# motoko_ice_dragon_x_bldc.net
KiCad netlist of a schematic drawn in EAGLE
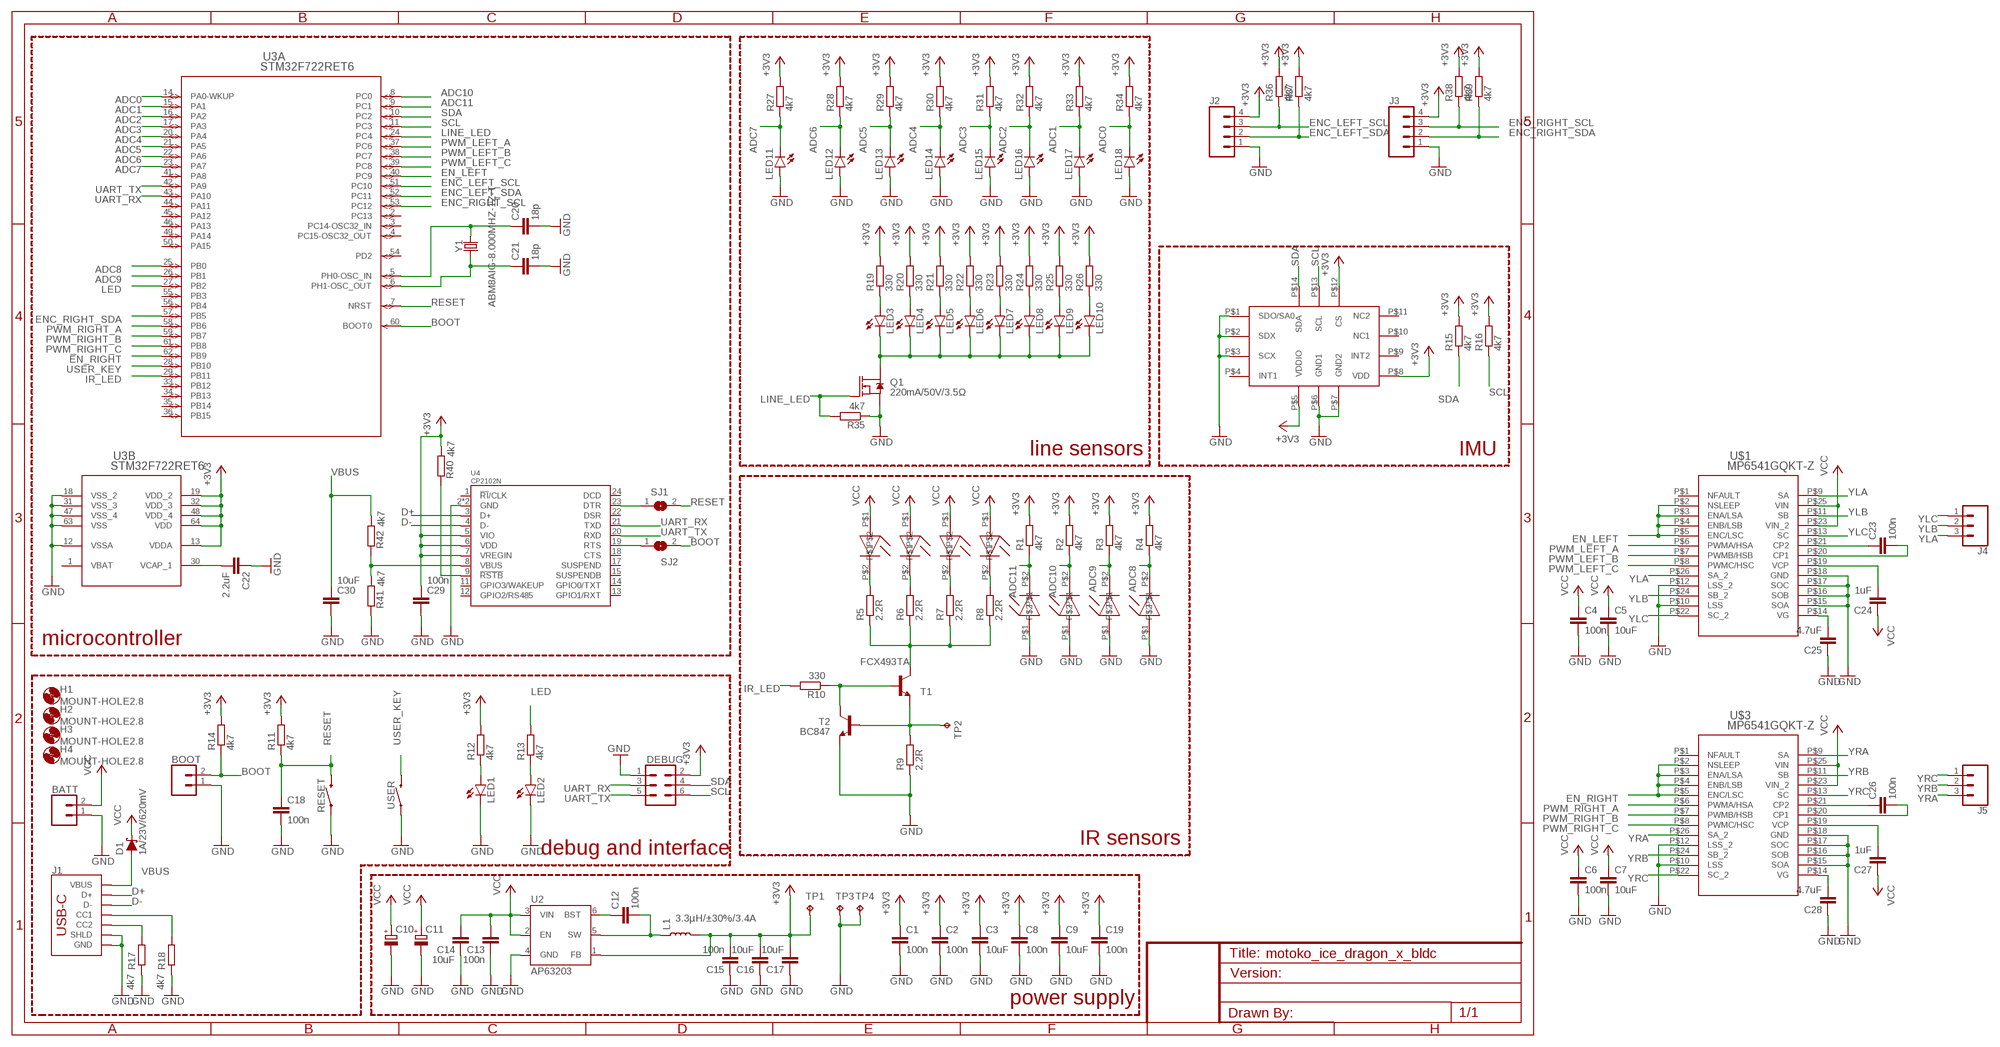
[diagram p0: schematic, sheet 1]

(export (version "E")
  (design (tool "Eeschema 10.0.6"))
  (components
    (comp (ref "BATT")
      (value "CONN_02LOCK_LONGPADS")
      (footprint "eagle-import:1X02_LOCK_LONGPADS")
      (libsource (lib "eagle-import") (part "CONN_02LOCK_LONGPADS"))
    )
    (comp (ref "BOOT")
      (value "CONN_02LOCK_LONGPADS")
      (footprint "eagle-import:1X02_LOCK_LONGPADS")
      (libsource (lib "eagle-import") (part "CONN_02LOCK_LONGPADS"))
    )
    (comp (ref "C1")
      (value "100n")
      (footprint "eagle-import:C0805")
      (libsource (lib "eagle-import") (part "C-EUC0805"))
    )
    (comp (ref "C2")
      (value "100n")
      (footprint "eagle-import:C0805")
      (libsource (lib "eagle-import") (part "C-EUC0805"))
    )
    (comp (ref "C3")
      (value "10uF")
      (footprint "eagle-import:C0805")
      (libsource (lib "eagle-import") (part "C-EUC0805"))
    )
    (comp (ref "C4")
      (value "100n")
      (footprint "eagle-import:C0805")
      (libsource (lib "eagle-import") (part "C-EUC0805"))
    )
    (comp (ref "C5")
      (value "10uF")
      (footprint "eagle-import:C0805")
      (libsource (lib "eagle-import") (part "C-EUC0805"))
    )
    (comp (ref "C6")
      (value "100n")
      (footprint "eagle-import:C0805")
      (libsource (lib "eagle-import") (part "C-EUC0805"))
    )
    (comp (ref "C7")
      (value "10uF")
      (footprint "eagle-import:C0805")
      (libsource (lib "eagle-import") (part "C-EUC0805"))
    )
    (comp (ref "C8")
      (value "100n")
      (footprint "eagle-import:C0805")
      (libsource (lib "eagle-import") (part "C-EUC0805"))
    )
    (comp (ref "C9")
      (value "10uF")
      (footprint "eagle-import:C0805")
      (libsource (lib "eagle-import") (part "C-EUC0805"))
    )
    (comp (ref "C10")
      (value "CPOL-EU140CLH-0810")
      (footprint "eagle-import:140CLH-0810")
      (libsource (lib "eagle-import") (part "CPOL-EU140CLH-0810"))
    )
    (comp (ref "C11")
      (value "CPOL-EU140CLH-0810")
      (footprint "eagle-import:140CLH-0810")
      (libsource (lib "eagle-import") (part "CPOL-EU140CLH-0810"))
    )
    (comp (ref "C12")
      (value "100n")
      (footprint "eagle-import:C0805")
      (libsource (lib "eagle-import") (part "C-EUC0805"))
    )
    (comp (ref "C13")
      (value "100n")
      (footprint "eagle-import:C0805")
      (libsource (lib "eagle-import") (part "C-EUC0805"))
    )
    (comp (ref "C14")
      (value "10uF")
      (footprint "eagle-import:C0805")
      (libsource (lib "eagle-import") (part "C-EUC0805"))
    )
    (comp (ref "C15")
      (value "100n")
      (footprint "eagle-import:C0805")
      (libsource (lib "eagle-import") (part "C-EUC0805"))
    )
    (comp (ref "C16")
      (value "10uF")
      (footprint "eagle-import:C0805")
      (libsource (lib "eagle-import") (part "C-EUC0805"))
    )
    (comp (ref "C17")
      (value "10uF")
      (footprint "eagle-import:C0805")
      (libsource (lib "eagle-import") (part "C-EUC0805"))
    )
    (comp (ref "C18")
      (value "100n")
      (footprint "eagle-import:C0805")
      (libsource (lib "eagle-import") (part "C-EUC0805"))
    )
    (comp (ref "C19")
      (value "100n")
      (footprint "eagle-import:C0805")
      (libsource (lib "eagle-import") (part "C-EUC0805"))
    )
    (comp (ref "C20")
      (value "18p")
      (footprint "eagle-import:C0805")
      (libsource (lib "eagle-import") (part "C-EUC0805"))
    )
    (comp (ref "C21")
      (value "18p")
      (footprint "eagle-import:C0805")
      (libsource (lib "eagle-import") (part "C-EUC0805"))
    )
    (comp (ref "C22")
      (value "2.2uF")
      (footprint "eagle-import:C0805")
      (libsource (lib "eagle-import") (part "C-EUC0805"))
    )
    (comp (ref "C23")
      (value "100n")
      (footprint "eagle-import:C0805")
      (libsource (lib "eagle-import") (part "C-EUC0805"))
    )
    (comp (ref "C24")
      (value "1uF")
      (footprint "eagle-import:C0805")
      (libsource (lib "eagle-import") (part "C-EUC0805"))
    )
    (comp (ref "C25")
      (value "4.7uF")
      (footprint "eagle-import:C0805")
      (libsource (lib "eagle-import") (part "C-EUC0805"))
    )
    (comp (ref "C26")
      (value "100n")
      (footprint "eagle-import:C0805")
      (libsource (lib "eagle-import") (part "C-EUC0805"))
    )
    (comp (ref "C27")
      (value "1uF")
      (footprint "eagle-import:C0805")
      (libsource (lib "eagle-import") (part "C-EUC0805"))
    )
    (comp (ref "C28")
      (value "4.7uF")
      (footprint "eagle-import:C0805")
      (libsource (lib "eagle-import") (part "C-EUC0805"))
    )
    (comp (ref "C29")
      (value "100n")
      (footprint "eagle-import:C0805")
      (libsource (lib "eagle-import") (part "C-EUC0805"))
    )
    (comp (ref "C30")
      (value "10uF")
      (footprint "eagle-import:C0805")
      (libsource (lib "eagle-import") (part "C-EUC0805"))
    )
    (comp (ref "D1")
      (value "1A/23V/620mV")
      (footprint "eagle-import:SOD-323")
      (libsource (lib "eagle-import") (part "DIODE-SCHOTTKY-BAT20J"))
    )
    (comp (ref "DEBUG")
      (value "FEMALE 2x3")
      (footprint "eagle-import:2X3")
      (libsource (lib "eagle-import") (part "CONN_03X2FEMALE"))
    )
    (comp (ref "H1")
      (value "MOUNT-HOLE2.8")
      (footprint "eagle-import:2,8")
      (libsource (lib "eagle-import") (part "MOUNT-HOLE2.8"))
    )
    (comp (ref "H2")
      (value "MOUNT-HOLE2.8")
      (footprint "eagle-import:2,8")
      (libsource (lib "eagle-import") (part "MOUNT-HOLE2.8"))
    )
    (comp (ref "H3")
      (value "MOUNT-HOLE2.8")
      (footprint "eagle-import:2,8")
      (libsource (lib "eagle-import") (part "MOUNT-HOLE2.8"))
    )
    (comp (ref "H4")
      (value "MOUNT-HOLE2.8")
      (footprint "eagle-import:2,8")
      (libsource (lib "eagle-import") (part "MOUNT-HOLE2.8"))
    )
    (comp (ref "J1")
      (value "640-USB4105-GF-A-120, man. GCT")
      (footprint "eagle-import:USB-C-16P-2LAYER-PADS")
      (libsource (lib "eagle-import") (part "USB_C_2-LAYER_PADS"))
    )
    (comp (ref "J2")
      (value "CONN_04LONGPADS")
      (footprint "eagle-import:1X04_LONGPADS")
      (libsource (lib "eagle-import") (part "CONN_04LONGPADS"))
    )
    (comp (ref "J3")
      (value "CONN_04LONGPADS")
      (footprint "eagle-import:1X04_LONGPADS")
      (libsource (lib "eagle-import") (part "CONN_04LONGPADS"))
    )
    (comp (ref "J4")
      (value "CONN_03LONGPADS")
      (footprint "eagle-import:1X03_LONGPADS")
      (libsource (lib "eagle-import") (part "CONN_03LONGPADS"))
    )
    (comp (ref "J5")
      (value "CONN_03LONGPADS")
      (footprint "eagle-import:1X03_LONGPADS")
      (libsource (lib "eagle-import") (part "CONN_03LONGPADS"))
    )
    (comp (ref "L1")
      (value "3.3µH/±30%/3.4A")
      (footprint "eagle-import:CR54")
      (libsource (lib "eagle-import") (part "INDUCTOR-CR54-3.3UH"))
    )
    (comp (ref "LED1")
      (value "LEDCHIPLED_1206")
      (footprint "eagle-import:CHIPLED_1206")
      (libsource (lib "eagle-import") (part "LEDCHIPLED_1206"))
    )
    (comp (ref "LED2")
      (value "LEDCHIPLED_1206")
      (footprint "eagle-import:CHIPLED_1206")
      (libsource (lib "eagle-import") (part "LEDCHIPLED_1206"))
    )
    (comp (ref "LED3")
      (value "LEDCHIPLED_1206")
      (footprint "eagle-import:CHIPLED_1206")
      (libsource (lib "eagle-import") (part "LEDCHIPLED_1206"))
    )
    (comp (ref "LED4")
      (value "LEDCHIPLED_1206")
      (footprint "eagle-import:CHIPLED_1206")
      (libsource (lib "eagle-import") (part "LEDCHIPLED_1206"))
    )
    (comp (ref "LED5")
      (value "LEDCHIPLED_1206")
      (footprint "eagle-import:CHIPLED_1206")
      (libsource (lib "eagle-import") (part "LEDCHIPLED_1206"))
    )
    (comp (ref "LED6")
      (value "LEDCHIPLED_1206")
      (footprint "eagle-import:CHIPLED_1206")
      (libsource (lib "eagle-import") (part "LEDCHIPLED_1206"))
    )
    (comp (ref "LED7")
      (value "LEDCHIPLED_1206")
      (footprint "eagle-import:CHIPLED_1206")
      (libsource (lib "eagle-import") (part "LEDCHIPLED_1206"))
    )
    (comp (ref "LED8")
      (value "LEDCHIPLED_1206")
      (footprint "eagle-import:CHIPLED_1206")
      (libsource (lib "eagle-import") (part "LEDCHIPLED_1206"))
    )
    (comp (ref "LED9")
      (value "LEDCHIPLED_1206")
      (footprint "eagle-import:CHIPLED_1206")
      (libsource (lib "eagle-import") (part "LEDCHIPLED_1206"))
    )
    (comp (ref "LED10")
      (value "LEDCHIPLED_1206")
      (footprint "eagle-import:CHIPLED_1206")
      (libsource (lib "eagle-import") (part "LEDCHIPLED_1206"))
    )
    (comp (ref "LED11")
      (value "LEDCHIPLED_1206")
      (footprint "eagle-import:CHIPLED_1206")
      (libsource (lib "eagle-import") (part "LEDCHIPLED_1206"))
    )
    (comp (ref "LED12")
      (value "LEDCHIPLED_1206")
      (footprint "eagle-import:CHIPLED_1206")
      (libsource (lib "eagle-import") (part "LEDCHIPLED_1206"))
    )
    (comp (ref "LED13")
      (value "LEDCHIPLED_1206")
      (footprint "eagle-import:CHIPLED_1206")
      (libsource (lib "eagle-import") (part "LEDCHIPLED_1206"))
    )
    (comp (ref "LED14")
      (value "LEDCHIPLED_1206")
      (footprint "eagle-import:CHIPLED_1206")
      (libsource (lib "eagle-import") (part "LEDCHIPLED_1206"))
    )
    (comp (ref "LED15")
      (value "LEDCHIPLED_1206")
      (footprint "eagle-import:CHIPLED_1206")
      (libsource (lib "eagle-import") (part "LEDCHIPLED_1206"))
    )
    (comp (ref "LED16")
      (value "LEDCHIPLED_1206")
      (footprint "eagle-import:CHIPLED_1206")
      (libsource (lib "eagle-import") (part "LEDCHIPLED_1206"))
    )
    (comp (ref "LED17")
      (value "LEDCHIPLED_1206")
      (footprint "eagle-import:CHIPLED_1206")
      (libsource (lib "eagle-import") (part "LEDCHIPLED_1206"))
    )
    (comp (ref "LED18")
      (value "LEDCHIPLED_1206")
      (footprint "eagle-import:CHIPLED_1206")
      (libsource (lib "eagle-import") (part "LEDCHIPLED_1206"))
    )
    (comp (ref "Q1")
      (value "220mA/50V/3.5Ω")
      (footprint "eagle-import:SOT23-3")
      (libsource (lib "eagle-import") (part "MOSFET-NCH-BSS138"))
    )
    (comp (ref "R1")
      (value "4k7")
      (footprint "eagle-import:M0805")
      (libsource (lib "eagle-import") (part "R-EU_M0805"))
    )
    (comp (ref "R2")
      (value "4k7")
      (footprint "eagle-import:M0805")
      (libsource (lib "eagle-import") (part "R-EU_M0805"))
    )
    (comp (ref "R3")
      (value "4k7")
      (footprint "eagle-import:M0805")
      (libsource (lib "eagle-import") (part "R-EU_M0805"))
    )
    (comp (ref "R4")
      (value "4k7")
      (footprint "eagle-import:M0805")
      (libsource (lib "eagle-import") (part "R-EU_M0805"))
    )
    (comp (ref "R5")
      (value "2.2R")
      (footprint "eagle-import:M0805")
      (libsource (lib "eagle-import") (part "R-EU_M0805"))
    )
    (comp (ref "R6")
      (value "2.2R")
      (footprint "eagle-import:M0805")
      (libsource (lib "eagle-import") (part "R-EU_M0805"))
    )
    (comp (ref "R7")
      (value "2.2R")
      (footprint "eagle-import:M0805")
      (libsource (lib "eagle-import") (part "R-EU_M0805"))
    )
    (comp (ref "R8")
      (value "2.2R")
      (footprint "eagle-import:M0805")
      (libsource (lib "eagle-import") (part "R-EU_M0805"))
    )
    (comp (ref "R9")
      (value "2.2R")
      (footprint "eagle-import:M0805")
      (libsource (lib "eagle-import") (part "R-EU_M0805"))
    )
    (comp (ref "R10")
      (value "330")
      (footprint "eagle-import:M0805")
      (libsource (lib "eagle-import") (part "R-EU_M0805"))
    )
    (comp (ref "R11")
      (value "4k7")
      (footprint "eagle-import:M0805")
      (libsource (lib "eagle-import") (part "R-EU_M0805"))
    )
    (comp (ref "R12")
      (value "4k7")
      (footprint "eagle-import:M0805")
      (libsource (lib "eagle-import") (part "R-EU_M0805"))
    )
    (comp (ref "R13")
      (value "4k7")
      (footprint "eagle-import:M0805")
      (libsource (lib "eagle-import") (part "R-EU_M0805"))
    )
    (comp (ref "R14")
      (value "4k7")
      (footprint "eagle-import:M0805")
      (libsource (lib "eagle-import") (part "R-EU_M0805"))
    )
    (comp (ref "R15")
      (value "4k7")
      (footprint "eagle-import:M0805")
      (libsource (lib "eagle-import") (part "R-EU_M0805"))
    )
    (comp (ref "R16")
      (value "4k7")
      (footprint "eagle-import:M0805")
      (libsource (lib "eagle-import") (part "R-EU_M0805"))
    )
    (comp (ref "R17")
      (value "4k7")
      (footprint "eagle-import:M0805")
      (libsource (lib "eagle-import") (part "R-EU_M0805"))
    )
    (comp (ref "R18")
      (value "4k7")
      (footprint "eagle-import:M0805")
      (libsource (lib "eagle-import") (part "R-EU_M0805"))
    )
    (comp (ref "R19")
      (value "330")
      (footprint "eagle-import:M0805")
      (libsource (lib "eagle-import") (part "R-EU_M0805"))
    )
    (comp (ref "R20")
      (value "330")
      (footprint "eagle-import:M0805")
      (libsource (lib "eagle-import") (part "R-EU_M0805"))
    )
    (comp (ref "R21")
      (value "330")
      (footprint "eagle-import:M0805")
      (libsource (lib "eagle-import") (part "R-EU_M0805"))
    )
    (comp (ref "R22")
      (value "330")
      (footprint "eagle-import:M0805")
      (libsource (lib "eagle-import") (part "R-EU_M0805"))
    )
    (comp (ref "R23")
      (value "330")
      (footprint "eagle-import:M0805")
      (libsource (lib "eagle-import") (part "R-EU_M0805"))
    )
    (comp (ref "R24")
      (value "330")
      (footprint "eagle-import:M0805")
      (libsource (lib "eagle-import") (part "R-EU_M0805"))
    )
    (comp (ref "R25")
      (value "330")
      (footprint "eagle-import:M0805")
      (libsource (lib "eagle-import") (part "R-EU_M0805"))
    )
    (comp (ref "R26")
      (value "330")
      (footprint "eagle-import:M0805")
      (libsource (lib "eagle-import") (part "R-EU_M0805"))
    )
    (comp (ref "R27")
      (value "4k7")
      (footprint "eagle-import:M0805")
      (libsource (lib "eagle-import") (part "R-EU_M0805"))
    )
    (comp (ref "R28")
      (value "4k7")
      (footprint "eagle-import:M0805")
      (libsource (lib "eagle-import") (part "R-EU_M0805"))
    )
    (comp (ref "R29")
      (value "4k7")
      (footprint "eagle-import:M0805")
      (libsource (lib "eagle-import") (part "R-EU_M0805"))
    )
    (comp (ref "R30")
      (value "4k7")
      (footprint "eagle-import:M0805")
      (libsource (lib "eagle-import") (part "R-EU_M0805"))
    )
    (comp (ref "R31")
      (value "4k7")
      (footprint "eagle-import:M0805")
      (libsource (lib "eagle-import") (part "R-EU_M0805"))
    )
    (comp (ref "R32")
      (value "4k7")
      (footprint "eagle-import:M0805")
      (libsource (lib "eagle-import") (part "R-EU_M0805"))
    )
    (comp (ref "R33")
      (value "4k7")
      (footprint "eagle-import:M0805")
      (libsource (lib "eagle-import") (part "R-EU_M0805"))
    )
    (comp (ref "R34")
      (value "4k7")
      (footprint "eagle-import:M0805")
      (libsource (lib "eagle-import") (part "R-EU_M0805"))
    )
    (comp (ref "R35")
      (value "4k7")
      (footprint "eagle-import:M0805")
      (libsource (lib "eagle-import") (part "R-EU_M0805"))
    )
    (comp (ref "R36")
      (value "4k7")
      (footprint "eagle-import:M0805")
      (libsource (lib "eagle-import") (part "R-EU_M0805"))
    )
    (comp (ref "R37")
      (value "4k7")
      (footprint "eagle-import:M0805")
      (libsource (lib "eagle-import") (part "R-EU_M0805"))
    )
    (comp (ref "R38")
      (value "4k7")
      (footprint "eagle-import:M0805")
      (libsource (lib "eagle-import") (part "R-EU_M0805"))
    )
    (comp (ref "R39")
      (value "4k7")
      (footprint "eagle-import:M0805")
      (libsource (lib "eagle-import") (part "R-EU_M0805"))
    )
    (comp (ref "R40")
      (value "4k7")
      (footprint "eagle-import:M0805")
      (libsource (lib "eagle-import") (part "R-EU_M0805"))
    )
    (comp (ref "R41")
      (value "4k7")
      (footprint "eagle-import:M0805")
      (libsource (lib "eagle-import") (part "R-EU_M0805"))
    )
    (comp (ref "R42")
      (value "4k7")
      (footprint "eagle-import:M0805")
      (libsource (lib "eagle-import") (part "R-EU_M0805"))
    )
    (comp (ref "RESET")
      (value "MOMENTARY-SWITCH-SPST-SMD-6.2MM-TALL")
      (footprint "eagle-import:TACTILE_SWITCH_SMD_6.2MM_TALL")
      (libsource (lib "eagle-import") (part "MOMENTARY-SWITCH-SPST-SMD-6.2MM-TALL"))
    )
    (comp (ref "SJ1") (value "SJ") (footprint "eagle-import:SJ") (libsource (lib "eagle-import") (part "SJ")))
    (comp (ref "SJ2") (value "SJ") (footprint "eagle-import:SJ") (libsource (lib "eagle-import") (part "SJ")))
    (comp (ref "T1")
      (value "FCX493TA")
      (footprint "eagle-import:SOT89-BCE")
      (libsource (lib "eagle-import") (part "-NPN-SOT89-BCE"))
    )
    (comp (ref "T2")
      (value "BC847")
      (footprint "eagle-import:SOT23")
      (libsource (lib "eagle-import") (part "BC847"))
    )
    (comp (ref "TP1")
      (value "TPB1,27")
      (footprint "eagle-import:B1,27")
      (libsource (lib "eagle-import") (part "TPB1,27"))
    )
    (comp (ref "TP2")
      (value "TPB1,27")
      (footprint "eagle-import:B1,27")
      (libsource (lib "eagle-import") (part "TPB1,27"))
    )
    (comp (ref "TP3")
      (value "TPB1,27")
      (footprint "eagle-import:B1,27")
      (libsource (lib "eagle-import") (part "TPB1,27"))
    )
    (comp (ref "TP4")
      (value "TPB1,27")
      (footprint "eagle-import:B1,27")
      (libsource (lib "eagle-import") (part "TPB1,27"))
    )
    (comp (ref "U$1")
      (value "MP6541GQKT-Z")
      (footprint "eagle-import:TQFN-26")
      (libsource (lib "eagle-import") (part "MP6541GQKT-Z"))
    )
    (comp (ref "U$3")
      (value "MP6541GQKT-Z")
      (footprint "eagle-import:TQFN-26")
      (libsource (lib "eagle-import") (part "MP6541GQKT-Z"))
    )
    (comp (ref "U$6")
      (value "LSM6DSM")
      (footprint "eagle-import:LGA14L")
      (libsource (lib "eagle-import") (part "LSM6DSM"))
    )
    (comp (ref "U$7")
      (value "LED_5MM_AXIAL")
      (footprint "eagle-import:LED_5MM_AXIAL")
      (libsource (lib "eagle-import") (part "LED_5MM_AXIAL"))
    )
    (comp (ref "U$8")
      (value "LED_5MM_AXIAL")
      (footprint "eagle-import:LED_5MM_AXIAL")
      (libsource (lib "eagle-import") (part "LED_5MM_AXIAL"))
    )
    (comp (ref "U$9")
      (value "LED_5MM_AXIAL")
      (footprint "eagle-import:LED_5MM_AXIAL")
      (libsource (lib "eagle-import") (part "LED_5MM_AXIAL"))
    )
    (comp (ref "U$10")
      (value "LED_5MM_AXIAL")
      (footprint "eagle-import:LED_5MM_AXIAL")
      (libsource (lib "eagle-import") (part "LED_5MM_AXIAL"))
    )
    (comp (ref "U$11")
      (value "LED_5MM_AXIAL")
      (footprint "eagle-import:LED_5MM_AXIAL")
      (libsource (lib "eagle-import") (part "LED_5MM_AXIAL"))
    )
    (comp (ref "U$12")
      (value "LED_5MM_AXIAL")
      (footprint "eagle-import:LED_5MM_AXIAL")
      (fields (field (name "SPICEPREFIX") "B"))
      (libsource (lib "eagle-import") (part "LED_5MM_AXIAL"))
    )
    (comp (ref "U$13")
      (value "LED_5MM_AXIAL")
      (footprint "eagle-import:LED_5MM_AXIAL")
      (libsource (lib "eagle-import") (part "LED_5MM_AXIAL"))
    )
    (comp (ref "U$14")
      (value "LED_5MM_AXIAL")
      (footprint "eagle-import:LED_5MM_AXIAL")
      (libsource (lib "eagle-import") (part "LED_5MM_AXIAL"))
    )
    (comp (ref "U2")
      (value "AP63203")
      (footprint "eagle-import:SOT23-6")
      (libsource (lib "eagle-import") (part "AP63203"))
    )
    (comp (ref "U3")
      (value "STM32F722RET6")
      (footprint "eagle-import:LQFP64-10X10MM")
      (fields (field (name "COPYRIGHT") "Copyright (C) 2024 Ultra Librarian. All rights reserved."))
      (libsource (lib "eagle-import") (part "STM32F722RET6"))
    )
    (comp (ref "U4")
      (value "CP2102N")
      (footprint "eagle-import:QFN24")
      (libsource (lib "eagle-import") (part "CP2102N"))
    )
    (comp (ref "USER")
      (value "MOMENTARY-SWITCH-SPST-SMD-6.2MM-TALL")
      (footprint "eagle-import:TACTILE_SWITCH_SMD_6.2MM_TALL")
      (libsource (lib "eagle-import") (part "MOMENTARY-SWITCH-SPST-SMD-6.2MM-TALL"))
    )
    (comp (ref "Y1")
      (value "ABM8AIG-8.000MHZ-1Z-T")
      (footprint "eagle-import:CRYSTAL-SMD-3.2X2.5MM")
      (libsource (lib "eagle-import") (part "CRYSTALSMD-3.2X2.5"))
    )
  )
  (nets
    (net (code "1") (name "+3V3") (class "Default")
      (node (ref "C1") (pin "1") (pinfunction "1_1") (pintype "passive"))
      (node (ref "C15") (pin "2") (pinfunction "2_2") (pintype "passive"))
      (node (ref "C16") (pin "2") (pinfunction "2_2") (pintype "passive"))
      (node (ref "C17") (pin "2") (pinfunction "2_2") (pintype "passive"))
      (node (ref "C19") (pin "1") (pinfunction "1_1") (pintype "passive"))
      (node (ref "C2") (pin "1") (pinfunction "1_1") (pintype "passive"))
      (node (ref "C29") (pin "1") (pinfunction "1_1") (pintype "passive"))
      (node (ref "C3") (pin "1") (pinfunction "1_1") (pintype "passive"))
      (node (ref "C8") (pin "1") (pinfunction "1_1") (pintype "passive"))
      (node (ref "C9") (pin "1") (pinfunction "1_1") (pintype "passive"))
      (node (ref "DEBUG") (pin "2") (pinfunction "2_2") (pintype "bidirectional"))
      (node (ref "J2") (pin "4") (pinfunction "4_4") (pintype "passive"))
      (node (ref "J3") (pin "4") (pinfunction "4_4") (pintype "passive"))
      (node (ref "L1") (pin "P$2") (pinfunction "2_P$2") (pintype "passive"))
      (node (ref "R1") (pin "2") (pinfunction "2_2") (pintype "passive"))
      (node (ref "R11") (pin "2") (pinfunction "2_2") (pintype "passive"))
      (node (ref "R12") (pin "2") (pinfunction "2_2") (pintype "passive"))
      (node (ref "R14") (pin "2") (pinfunction "2_2") (pintype "passive"))
      (node (ref "R15") (pin "2") (pinfunction "2_2") (pintype "passive"))
      (node (ref "R16") (pin "2") (pinfunction "2_2") (pintype "passive"))
      (node (ref "R19") (pin "2") (pinfunction "2_2") (pintype "passive"))
      (node (ref "R2") (pin "2") (pinfunction "2_2") (pintype "passive"))
      (node (ref "R20") (pin "2") (pinfunction "2_2") (pintype "passive"))
      (node (ref "R21") (pin "2") (pinfunction "2_2") (pintype "passive"))
      (node (ref "R22") (pin "2") (pinfunction "2_2") (pintype "passive"))
      (node (ref "R23") (pin "2") (pinfunction "2_2") (pintype "passive"))
      (node (ref "R24") (pin "2") (pinfunction "2_2") (pintype "passive"))
      (node (ref "R25") (pin "2") (pinfunction "2_2") (pintype "passive"))
      (node (ref "R26") (pin "2") (pinfunction "2_2") (pintype "passive"))
      (node (ref "R27") (pin "2") (pinfunction "2_2") (pintype "passive"))
      (node (ref "R28") (pin "2") (pinfunction "2_2") (pintype "passive"))
      (node (ref "R29") (pin "2") (pinfunction "2_2") (pintype "passive"))
      (node (ref "R3") (pin "2") (pinfunction "2_2") (pintype "passive"))
      (node (ref "R30") (pin "2") (pinfunction "2_2") (pintype "passive"))
      (node (ref "R31") (pin "2") (pinfunction "2_2") (pintype "passive"))
      (node (ref "R32") (pin "2") (pinfunction "2_2") (pintype "passive"))
      (node (ref "R33") (pin "2") (pinfunction "2_2") (pintype "passive"))
      (node (ref "R34") (pin "2") (pinfunction "2_2") (pintype "passive"))
      (node (ref "R36") (pin "2") (pinfunction "2_2") (pintype "passive"))
      (node (ref "R37") (pin "2") (pinfunction "2_2") (pintype "passive"))
      (node (ref "R38") (pin "2") (pinfunction "2_2") (pintype "passive"))
      (node (ref "R39") (pin "2") (pinfunction "2_2") (pintype "passive"))
      (node (ref "R4") (pin "2") (pinfunction "2_2") (pintype "passive"))
      (node (ref "R40") (pin "1") (pinfunction "1_1") (pintype "passive"))
      (node (ref "TP1") (pin "TP") (pinfunction "TP_TP") (pintype "input"))
      (node (ref "U$6") (pin "P$12") (pinfunction "CS_P$12") (pintype "bidirectional"))
      (node (ref "U$6") (pin "P$5") (pinfunction "VDDIO_P$5") (pintype "bidirectional"))
      (node (ref "U$6") (pin "P$8") (pinfunction "VDD_P$8") (pintype "bidirectional"))
      (node (ref "U2") (pin "1") (pinfunction "FB_1") (pintype "bidirectional"))
      (node (ref "U3") (pin "13") (pinfunction "VDDA_13") (pintype "power_in"))
      (node (ref "U3") (pin "19") (pinfunction "VDD_2_19") (pintype "power_in"))
      (node (ref "U3") (pin "32") (pinfunction "VDD_3_32") (pintype "power_in"))
      (node (ref "U3") (pin "48") (pinfunction "VDD_4_48") (pintype "power_in"))
      (node (ref "U3") (pin "64") (pinfunction "VDD_64") (pintype "power_in"))
      (node (ref "U4") (pin "5") (pinfunction "VIO_5") (pintype "bidirectional"))
      (node (ref "U4") (pin "6") (pinfunction "VDD_6") (pintype "bidirectional"))
      (node (ref "U4") (pin "7") (pinfunction "VREGIN_7") (pintype "bidirectional"))
    )
    (net (code "2") (name "/ADC0") (class "Default")
      (node (ref "LED18") (pin "C") (pinfunction "C_C") (pintype "passive"))
      (node (ref "R34") (pin "1") (pinfunction "1_1") (pintype "passive"))
      (node (ref "U3") (pin "14") (pinfunction "PA0-WKUP_14") (pintype "bidirectional"))
    )
    (net (code "3") (name "/ADC1") (class "Default")
      (node (ref "LED17") (pin "C") (pinfunction "C_C") (pintype "passive"))
      (node (ref "R33") (pin "1") (pinfunction "1_1") (pintype "passive"))
      (node (ref "U3") (pin "15") (pinfunction "PA1_15") (pintype "bidirectional"))
    )
    (net (code "4") (name "/ADC2") (class "Default")
      (node (ref "LED16") (pin "C") (pinfunction "C_C") (pintype "passive"))
      (node (ref "R32") (pin "1") (pinfunction "1_1") (pintype "passive"))
      (node (ref "U3") (pin "16") (pinfunction "PA2_16") (pintype "bidirectional"))
    )
    (net (code "5") (name "/ADC3") (class "Default")
      (node (ref "LED15") (pin "C") (pinfunction "C_C") (pintype "passive"))
      (node (ref "R31") (pin "1") (pinfunction "1_1") (pintype "passive"))
      (node (ref "U3") (pin "17") (pinfunction "PA3_17") (pintype "bidirectional"))
    )
    (net (code "6") (name "/ADC4") (class "Default")
      (node (ref "LED14") (pin "C") (pinfunction "C_C") (pintype "passive"))
      (node (ref "R30") (pin "1") (pinfunction "1_1") (pintype "passive"))
      (node (ref "U3") (pin "20") (pinfunction "PA4_20") (pintype "bidirectional"))
    )
    (net (code "7") (name "/ADC5") (class "Default")
      (node (ref "LED13") (pin "C") (pinfunction "C_C") (pintype "passive"))
      (node (ref "R29") (pin "1") (pinfunction "1_1") (pintype "passive"))
      (node (ref "U3") (pin "21") (pinfunction "PA5_21") (pintype "bidirectional"))
    )
    (net (code "8") (name "/ADC6") (class "Default")
      (node (ref "LED12") (pin "C") (pinfunction "C_C") (pintype "passive"))
      (node (ref "R28") (pin "1") (pinfunction "1_1") (pintype "passive"))
      (node (ref "U3") (pin "22") (pinfunction "PA6_22") (pintype "bidirectional"))
    )
    (net (code "9") (name "/ADC7") (class "Default")
      (node (ref "LED11") (pin "C") (pinfunction "C_C") (pintype "passive"))
      (node (ref "R27") (pin "1") (pinfunction "1_1") (pintype "passive"))
      (node (ref "U3") (pin "23") (pinfunction "PA7_23") (pintype "bidirectional"))
    )
    (net (code "10") (name "/ADC8") (class "Default")
      (node (ref "R4") (pin "1") (pinfunction "1_1") (pintype "passive"))
      (node (ref "U$7") (pin "P$2") (pinfunction "P$2_P$2") (pintype "bidirectional"))
      (node (ref "U3") (pin "25") (pinfunction "PB0_25") (pintype "bidirectional"))
    )
    (net (code "11") (name "/ADC9") (class "Default")
      (node (ref "R3") (pin "1") (pinfunction "1_1") (pintype "passive"))
      (node (ref "U$11") (pin "P$2") (pinfunction "P$2_P$2") (pintype "bidirectional"))
      (node (ref "U3") (pin "26") (pinfunction "PB1_26") (pintype "bidirectional"))
    )
    (net (code "12") (name "/ADC10") (class "Default")
      (node (ref "R2") (pin "1") (pinfunction "1_1") (pintype "passive"))
      (node (ref "U$14") (pin "P$2") (pinfunction "P$2_P$2") (pintype "bidirectional"))
      (node (ref "U3") (pin "8") (pinfunction "PC0_8") (pintype "bidirectional"))
    )
    (net (code "13") (name "/ADC11") (class "Default")
      (node (ref "R1") (pin "1") (pinfunction "1_1") (pintype "passive"))
      (node (ref "U$9") (pin "P$2") (pinfunction "P$2_P$2") (pintype "bidirectional"))
      (node (ref "U3") (pin "9") (pinfunction "PC1_9") (pintype "bidirectional"))
    )
    (net (code "14") (name "/BOOT") (class "Default")
      (node (ref "BOOT") (pin "2") (pinfunction "2_2") (pintype "passive"))
      (node (ref "R14") (pin "1") (pinfunction "1_1") (pintype "passive"))
      (node (ref "SJ2") (pin "2") (pinfunction "2_2") (pintype "passive"))
      (node (ref "U3") (pin "60") (pinfunction "BOOT0_60") (pintype "input"))
    )
    (net (code "15") (name "/D+") (class "Default")
      (node (ref "J1") (pin "A6") (pinfunction "D+_A6") (pintype "bidirectional"))
      (node (ref "J1") (pin "B6") (pinfunction "D+_B6") (pintype "bidirectional"))
      (node (ref "U4") (pin "3") (pinfunction "D+_3") (pintype "bidirectional"))
    )
    (net (code "16") (name "/D-") (class "Default")
      (node (ref "J1") (pin "A7") (pinfunction "D-_A7") (pintype "bidirectional"))
      (node (ref "J1") (pin "B7") (pinfunction "D-_B7") (pintype "bidirectional"))
      (node (ref "U4") (pin "4") (pinfunction "D-_4") (pintype "bidirectional"))
    )
    (net (code "17") (name "/ENC_LEFT_SCL") (class "Default")
      (node (ref "J2") (pin "3") (pinfunction "3_3") (pintype "passive"))
      (node (ref "R36") (pin "1") (pinfunction "1_1") (pintype "passive"))
      (node (ref "U3") (pin "51") (pinfunction "PC10_51") (pintype "bidirectional"))
    )
    (net (code "18") (name "/ENC_LEFT_SDA") (class "Default")
      (node (ref "J2") (pin "2") (pinfunction "2_2") (pintype "passive"))
      (node (ref "R37") (pin "1") (pinfunction "1_1") (pintype "passive"))
      (node (ref "U3") (pin "52") (pinfunction "PC11_52") (pintype "bidirectional"))
    )
    (net (code "19") (name "/ENC_RIGHT_SCL") (class "Default")
      (node (ref "J3") (pin "3") (pinfunction "3_3") (pintype "passive"))
      (node (ref "R38") (pin "1") (pinfunction "1_1") (pintype "passive"))
      (node (ref "U3") (pin "53") (pinfunction "PC12_53") (pintype "bidirectional"))
    )
    (net (code "20") (name "/ENC_RIGHT_SDA") (class "Default")
      (node (ref "J3") (pin "2") (pinfunction "2_2") (pintype "passive"))
      (node (ref "R39") (pin "1") (pinfunction "1_1") (pintype "passive"))
      (node (ref "U3") (pin "57") (pinfunction "PB5_57") (pintype "bidirectional"))
    )
    (net (code "21") (name "/EN_LEFT") (class "Default")
      (node (ref "U$1") (pin "P$2") (pinfunction "NSLEEP_P$2") (pintype "input"))
      (node (ref "U$1") (pin "P$3") (pinfunction "ENA/LSA_P$3") (pintype "passive"))
      (node (ref "U$1") (pin "P$4") (pinfunction "ENB/LSB_P$4") (pintype "passive"))
      (node (ref "U$1") (pin "P$5") (pinfunction "ENC/LSC_P$5") (pintype "passive"))
      (node (ref "U3") (pin "40") (pinfunction "PC9_40") (pintype "bidirectional"))
    )
    (net (code "22") (name "/EN_RIGHT") (class "Default")
      (node (ref "U$3") (pin "P$2") (pinfunction "NSLEEP_P$2") (pintype "input"))
      (node (ref "U$3") (pin "P$3") (pinfunction "ENA/LSA_P$3") (pintype "passive"))
      (node (ref "U$3") (pin "P$4") (pinfunction "ENB/LSB_P$4") (pintype "passive"))
      (node (ref "U$3") (pin "P$5") (pinfunction "ENC/LSC_P$5") (pintype "passive"))
      (node (ref "U3") (pin "62") (pinfunction "PB9_62") (pintype "bidirectional"))
    )
    (net (code "23") (name "/IR_LED") (class "Default")
      (node (ref "R10") (pin "2") (pinfunction "2_2") (pintype "passive"))
      (node (ref "U3") (pin "29") (pinfunction "PB11_29") (pintype "bidirectional"))
    )
    (net (code "24") (name "/LED") (class "Default")
      (node (ref "R13") (pin "2") (pinfunction "2_2") (pintype "passive"))
      (node (ref "U3") (pin "27") (pinfunction "PB2_27") (pintype "bidirectional"))
    )
    (net (code "25") (name "/LINE_LED") (class "Default")
      (node (ref "Q1") (pin "1") (pinfunction "G_1") (pintype "bidirectional"))
      (node (ref "R35") (pin "2") (pinfunction "2_2") (pintype "passive"))
      (node (ref "U3") (pin "24") (pinfunction "PC4_24") (pintype "bidirectional"))
    )
    (net (code "26") (name "/PWM_LEFT_A") (class "Default")
      (node (ref "U$1") (pin "P$6") (pinfunction "PWMA/HSA_P$6") (pintype "passive"))
      (node (ref "U3") (pin "37") (pinfunction "PC6_37") (pintype "bidirectional"))
    )
    (net (code "27") (name "/PWM_LEFT_B") (class "Default")
      (node (ref "U$1") (pin "P$7") (pinfunction "PWMB/HSB_P$7") (pintype "passive"))
      (node (ref "U3") (pin "38") (pinfunction "PC7_38") (pintype "bidirectional"))
    )
    (net (code "28") (name "/PWM_LEFT_C") (class "Default")
      (node (ref "U$1") (pin "P$8") (pinfunction "PWMC/HSC_P$8") (pintype "passive"))
      (node (ref "U3") (pin "39") (pinfunction "PC8_39") (pintype "bidirectional"))
    )
    (net (code "29") (name "/PWM_RIGHT_A") (class "Default")
      (node (ref "U$3") (pin "P$6") (pinfunction "PWMA/HSA_P$6") (pintype "passive"))
      (node (ref "U3") (pin "58") (pinfunction "PB6_58") (pintype "bidirectional"))
    )
    (net (code "30") (name "/PWM_RIGHT_B") (class "Default")
      (node (ref "U$3") (pin "P$7") (pinfunction "PWMB/HSB_P$7") (pintype "passive"))
      (node (ref "U3") (pin "59") (pinfunction "PB7_59") (pintype "bidirectional"))
    )
    (net (code "31") (name "/PWM_RIGHT_C") (class "Default")
      (node (ref "U$3") (pin "P$8") (pinfunction "PWMC/HSC_P$8") (pintype "passive"))
      (node (ref "U3") (pin "61") (pinfunction "PB8_61") (pintype "bidirectional"))
    )
    (net (code "32") (name "/RESET") (class "Default")
      (node (ref "C18") (pin "1") (pinfunction "1_1") (pintype "passive"))
      (node (ref "R11") (pin "1") (pinfunction "1_1") (pintype "passive"))
      (node (ref "RESET") (pin "B2") (pinfunction "2_B2") (pintype "passive"))
      (node (ref "SJ1") (pin "2") (pinfunction "2_2") (pintype "passive"))
      (node (ref "U3") (pin "7") (pinfunction "NRST_7") (pintype "bidirectional"))
    )
    (net (code "33") (name "/SCL") (class "Default")
      (node (ref "DEBUG") (pin "6") (pinfunction "6_6") (pintype "bidirectional"))
      (node (ref "R16") (pin "1") (pinfunction "1_1") (pintype "passive"))
      (node (ref "U$6") (pin "P$13") (pinfunction "SCL_P$13") (pintype "bidirectional"))
      (node (ref "U3") (pin "11") (pinfunction "PC3_11") (pintype "bidirectional"))
    )
    (net (code "34") (name "/SDA") (class "Default")
      (node (ref "DEBUG") (pin "4") (pinfunction "4_4") (pintype "bidirectional"))
      (node (ref "R15") (pin "1") (pinfunction "1_1") (pintype "passive"))
      (node (ref "U$6") (pin "P$14") (pinfunction "SDA_P$14") (pintype "bidirectional"))
      (node (ref "U3") (pin "10") (pinfunction "PC2_10") (pintype "bidirectional"))
    )
    (net (code "35") (name "/UART_RX") (class "Default")
      (node (ref "DEBUG") (pin "3") (pinfunction "3_3") (pintype "bidirectional"))
      (node (ref "U3") (pin "43") (pinfunction "PA10_43") (pintype "bidirectional"))
      (node (ref "U4") (pin "21") (pinfunction "TXD_21") (pintype "bidirectional"))
    )
    (net (code "36") (name "/UART_TX") (class "Default")
      (node (ref "DEBUG") (pin "5") (pinfunction "5_5") (pintype "bidirectional"))
      (node (ref "U3") (pin "42") (pinfunction "PA9_42") (pintype "bidirectional"))
      (node (ref "U4") (pin "20") (pinfunction "RXD_20") (pintype "bidirectional"))
    )
    (net (code "37") (name "/USER_KEY") (class "Default")
      (node (ref "U3") (pin "28") (pinfunction "PB10_28") (pintype "bidirectional"))
      (node (ref "USER") (pin "B2") (pinfunction "2_B2") (pintype "passive"))
    )
    (net (code "38") (name "/VBAT") (class "Default")
      (node (ref "U3") (pin "1") (pinfunction "VBAT_1") (pintype "power_in"))
    )
    (net (code "39") (name "/VBUS") (class "Default")
      (node (ref "C30") (pin "1") (pinfunction "1_1") (pintype "passive"))
      (node (ref "D1") (pin "A") (pinfunction "A_A") (pintype "passive"))
      (node (ref "J1") (pin "VBUS1") (pinfunction "VBUS_VBUS1") (pintype "bidirectional"))
      (node (ref "J1") (pin "VBUS2") (pinfunction "VBUS_VBUS2") (pintype "bidirectional"))
      (node (ref "R42") (pin "1") (pinfunction "1_1") (pintype "passive"))
    )
    (net (code "40") (name "/YLA") (class "Default")
      (node (ref "J4") (pin "3") (pinfunction "3_3") (pintype "passive"))
      (node (ref "U$1") (pin "P$26") (pinfunction "SA_2_P$26") (pintype "output"))
      (node (ref "U$1") (pin "P$9") (pinfunction "SA_P$9") (pintype "output"))
    )
    (net (code "41") (name "/YLB") (class "Default")
      (node (ref "J4") (pin "2") (pinfunction "2_2") (pintype "passive"))
      (node (ref "U$1") (pin "P$11") (pinfunction "SB_P$11") (pintype "output"))
      (node (ref "U$1") (pin "P$24") (pinfunction "SB_2_P$24") (pintype "output"))
    )
    (net (code "42") (name "/YLC") (class "Default")
      (node (ref "J4") (pin "1") (pinfunction "1_1") (pintype "passive"))
      (node (ref "U$1") (pin "P$13") (pinfunction "SC_P$13") (pintype "output"))
      (node (ref "U$1") (pin "P$22") (pinfunction "SC_2_P$22") (pintype "output"))
    )
    (net (code "43") (name "/YRA") (class "Default")
      (node (ref "J5") (pin "3") (pinfunction "3_3") (pintype "passive"))
      (node (ref "U$3") (pin "P$26") (pinfunction "SA_2_P$26") (pintype "output"))
      (node (ref "U$3") (pin "P$9") (pinfunction "SA_P$9") (pintype "output"))
    )
    (net (code "44") (name "/YRB") (class "Default")
      (node (ref "J5") (pin "2") (pinfunction "2_2") (pintype "passive"))
      (node (ref "U$3") (pin "P$11") (pinfunction "SB_P$11") (pintype "output"))
      (node (ref "U$3") (pin "P$24") (pinfunction "SB_2_P$24") (pintype "output"))
    )
    (net (code "45") (name "/YRC") (class "Default")
      (node (ref "J5") (pin "1") (pinfunction "1_1") (pintype "passive"))
      (node (ref "U$3") (pin "P$13") (pinfunction "SC_P$13") (pintype "output"))
      (node (ref "U$3") (pin "P$22") (pinfunction "SC_2_P$22") (pintype "output"))
    )
    (net (code "46") (name "GND") (class "Default")
      (node (ref "BATT") (pin "1") (pinfunction "1_1") (pintype "passive"))
      (node (ref "BOOT") (pin "1") (pinfunction "1_1") (pintype "passive"))
      (node (ref "C1") (pin "2") (pinfunction "2_2") (pintype "passive"))
      (node (ref "C10") (pin "-") (pinfunction "-_-") (pintype "passive"))
      (node (ref "C11") (pin "-") (pinfunction "-_-") (pintype "passive"))
      (node (ref "C13") (pin "1") (pinfunction "1_1") (pintype "passive"))
      (node (ref "C14") (pin "1") (pinfunction "1_1") (pintype "passive"))
      (node (ref "C15") (pin "1") (pinfunction "1_1") (pintype "passive"))
      (node (ref "C16") (pin "1") (pinfunction "1_1") (pintype "passive"))
      (node (ref "C17") (pin "1") (pinfunction "1_1") (pintype "passive"))
      (node (ref "C18") (pin "2") (pinfunction "2_2") (pintype "passive"))
      (node (ref "C19") (pin "2") (pinfunction "2_2") (pintype "passive"))
      (node (ref "C2") (pin "2") (pinfunction "2_2") (pintype "passive"))
      (node (ref "C20") (pin "2") (pinfunction "2_2") (pintype "passive"))
      (node (ref "C21") (pin "2") (pinfunction "2_2") (pintype "passive"))
      (node (ref "C22") (pin "1") (pinfunction "1_1") (pintype "passive"))
      (node (ref "C25") (pin "1") (pinfunction "1_1") (pintype "passive"))
      (node (ref "C28") (pin "1") (pinfunction "1_1") (pintype "passive"))
      (node (ref "C29") (pin "2") (pinfunction "2_2") (pintype "passive"))
      (node (ref "C3") (pin "2") (pinfunction "2_2") (pintype "passive"))
      (node (ref "C30") (pin "2") (pinfunction "2_2") (pintype "passive"))
      (node (ref "C4") (pin "2") (pinfunction "2_2") (pintype "passive"))
      (node (ref "C5") (pin "2") (pinfunction "2_2") (pintype "passive"))
      (node (ref "C6") (pin "2") (pinfunction "2_2") (pintype "passive"))
      (node (ref "C7") (pin "2") (pinfunction "2_2") (pintype "passive"))
      (node (ref "C8") (pin "2") (pinfunction "2_2") (pintype "passive"))
      (node (ref "C9") (pin "2") (pinfunction "2_2") (pintype "passive"))
      (node (ref "DEBUG") (pin "1") (pinfunction "1_1") (pintype "bidirectional"))
      (node (ref "J1") (pin "GND") (pinfunction "GND_GND") (pintype "bidirectional"))
      (node (ref "J1") (pin "GND2") (pinfunction "GND_GND2") (pintype "bidirectional"))
      (node (ref "J1") (pin "SHLD1") (pinfunction "SHLD_SHLD1") (pintype "bidirectional"))
      (node (ref "J1") (pin "SHLD2") (pinfunction "SHLD_SHLD2") (pintype "bidirectional"))
      (node (ref "J1") (pin "SHLD3") (pinfunction "SHLD_SHLD3") (pintype "bidirectional"))
      (node (ref "J1") (pin "SHLD4") (pinfunction "SHLD_SHLD4") (pintype "bidirectional"))
      (node (ref "J2") (pin "1") (pinfunction "1_1") (pintype "passive"))
      (node (ref "J3") (pin "1") (pinfunction "1_1") (pintype "passive"))
      (node (ref "LED1") (pin "C") (pinfunction "C_C") (pintype "passive"))
      (node (ref "LED11") (pin "A") (pinfunction "A_A") (pintype "passive"))
      (node (ref "LED12") (pin "A") (pinfunction "A_A") (pintype "passive"))
      (node (ref "LED13") (pin "A") (pinfunction "A_A") (pintype "passive"))
      (node (ref "LED14") (pin "A") (pinfunction "A_A") (pintype "passive"))
      (node (ref "LED15") (pin "A") (pinfunction "A_A") (pintype "passive"))
      (node (ref "LED16") (pin "A") (pinfunction "A_A") (pintype "passive"))
      (node (ref "LED17") (pin "A") (pinfunction "A_A") (pintype "passive"))
      (node (ref "LED18") (pin "A") (pinfunction "A_A") (pintype "passive"))
      (node (ref "LED2") (pin "C") (pinfunction "C_C") (pintype "passive"))
      (node (ref "Q1") (pin "2") (pinfunction "S_2") (pintype "bidirectional"))
      (node (ref "R17") (pin "1") (pinfunction "1_1") (pintype "passive"))
      (node (ref "R18") (pin "1") (pinfunction "1_1") (pintype "passive"))
      (node (ref "R35") (pin "1") (pinfunction "1_1") (pintype "passive"))
      (node (ref "R41") (pin "2") (pinfunction "2_2") (pintype "passive"))
      (node (ref "R9") (pin "1") (pinfunction "1_1") (pintype "passive"))
      (node (ref "RESET") (pin "A2") (pinfunction "1_A2") (pintype "passive"))
      (node (ref "T2") (pin "2") (pinfunction "E_2") (pintype "passive"))
      (node (ref "TP3") (pin "TP") (pinfunction "TP_TP") (pintype "input"))
      (node (ref "TP4") (pin "TP") (pinfunction "TP_TP") (pintype "input"))
      (node (ref "U$1") (pin "P$10") (pinfunction "LSS_P$10") (pintype "passive"))
      (node (ref "U$1") (pin "P$12") (pinfunction "LSS_2_P$12") (pintype "passive"))
      (node (ref "U$1") (pin "P$15") (pinfunction "SOA_P$15") (pintype "output"))
      (node (ref "U$1") (pin "P$16") (pinfunction "SOB_P$16") (pintype "output"))
      (node (ref "U$1") (pin "P$17") (pinfunction "SOC_P$17") (pintype "output"))
      (node (ref "U$1") (pin "P$18") (pinfunction "GND_P$18") (pintype "passive"))
      (node (ref "U$11") (pin "P$1") (pinfunction "P$1_P$1") (pintype "bidirectional"))
      (node (ref "U$14") (pin "P$1") (pinfunction "P$1_P$1") (pintype "bidirectional"))
      (node (ref "U$3") (pin "P$10") (pinfunction "LSS_P$10") (pintype "passive"))
      (node (ref "U$3") (pin "P$12") (pinfunction "LSS_2_P$12") (pintype "passive"))
      (node (ref "U$3") (pin "P$15") (pinfunction "SOA_P$15") (pintype "output"))
      (node (ref "U$3") (pin "P$16") (pinfunction "SOB_P$16") (pintype "output"))
      (node (ref "U$3") (pin "P$17") (pinfunction "SOC_P$17") (pintype "output"))
      (node (ref "U$3") (pin "P$18") (pinfunction "GND_P$18") (pintype "passive"))
      (node (ref "U$6") (pin "P$1") (pinfunction "SDO/SA0_P$1") (pintype "bidirectional"))
      (node (ref "U$6") (pin "P$2") (pinfunction "SDX_P$2") (pintype "bidirectional"))
      (node (ref "U$6") (pin "P$3") (pinfunction "SCX_P$3") (pintype "bidirectional"))
      (node (ref "U$6") (pin "P$6") (pinfunction "GND1_P$6") (pintype "bidirectional"))
      (node (ref "U$6") (pin "P$7") (pinfunction "GND2_P$7") (pintype "bidirectional"))
      (node (ref "U$7") (pin "P$1") (pinfunction "P$1_P$1") (pintype "bidirectional"))
      (node (ref "U$9") (pin "P$1") (pinfunction "P$1_P$1") (pintype "bidirectional"))
      (node (ref "U2") (pin "4") (pinfunction "GND_4") (pintype "bidirectional"))
      (node (ref "U3") (pin "12") (pinfunction "VSSA_12") (pintype "power_in"))
      (node (ref "U3") (pin "18") (pinfunction "VSS_2_18") (pintype "power_in"))
      (node (ref "U3") (pin "31") (pinfunction "VSS_3_31") (pintype "power_in"))
      (node (ref "U3") (pin "47") (pinfunction "VSS_4_47") (pintype "power_in"))
      (node (ref "U3") (pin "63") (pinfunction "VSS_63") (pintype "power_in"))
      (node (ref "U4") (pin "2") (pinfunction "GND_2") (pintype "bidirectional"))
      (node (ref "U4") (pin "PAD") (pinfunction "GND_PAD") (pintype "bidirectional"))
      (node (ref "USER") (pin "A2") (pinfunction "1_A2") (pintype "passive"))
    )
    (net (code "47") (name "Net-(J1-CC1)") (class "Default")
      (node (ref "J1") (pin "A5") (pinfunction "CC1_A5") (pintype "bidirectional"))
      (node (ref "R18") (pin "2") (pinfunction "2_2") (pintype "passive"))
    )
    (net (code "48") (name "Net-(J1-CC2)") (class "Default")
      (node (ref "J1") (pin "B5") (pinfunction "CC2_B5") (pintype "bidirectional"))
      (node (ref "R17") (pin "2") (pinfunction "2_2") (pintype "passive"))
    )
    (net (code "49") (name "Net-(L1-1)") (class "Default")
      (node (ref "C12") (pin "2") (pinfunction "2_2") (pintype "passive"))
      (node (ref "L1") (pin "P$1") (pinfunction "1_P$1") (pintype "passive"))
      (node (ref "U2") (pin "5") (pinfunction "SW_5") (pintype "bidirectional"))
    )
    (net (code "50") (name "Net-(LED1-PadA)") (class "Default")
      (node (ref "LED1") (pin "A") (pinfunction "A_A") (pintype "passive"))
      (node (ref "R12") (pin "1") (pinfunction "1_1") (pintype "passive"))
    )
    (net (code "51") (name "Net-(LED2-PadA)") (class "Default")
      (node (ref "LED2") (pin "A") (pinfunction "A_A") (pintype "passive"))
      (node (ref "R13") (pin "1") (pinfunction "1_1") (pintype "passive"))
    )
    (net (code "52") (name "Net-(LED3-PadA)") (class "Default")
      (node (ref "LED3") (pin "A") (pinfunction "A_A") (pintype "passive"))
      (node (ref "R19") (pin "1") (pinfunction "1_1") (pintype "passive"))
    )
    (net (code "53") (name "Net-(LED4-PadA)") (class "Default")
      (node (ref "LED4") (pin "A") (pinfunction "A_A") (pintype "passive"))
      (node (ref "R20") (pin "1") (pinfunction "1_1") (pintype "passive"))
    )
    (net (code "54") (name "Net-(LED5-PadA)") (class "Default")
      (node (ref "LED5") (pin "A") (pinfunction "A_A") (pintype "passive"))
      (node (ref "R21") (pin "1") (pinfunction "1_1") (pintype "passive"))
    )
    (net (code "55") (name "Net-(LED6-PadA)") (class "Default")
      (node (ref "LED6") (pin "A") (pinfunction "A_A") (pintype "passive"))
      (node (ref "R22") (pin "1") (pinfunction "1_1") (pintype "passive"))
    )
    (net (code "56") (name "Net-(LED7-PadA)") (class "Default")
      (node (ref "LED7") (pin "A") (pinfunction "A_A") (pintype "passive"))
      (node (ref "R23") (pin "1") (pinfunction "1_1") (pintype "passive"))
    )
    (net (code "57") (name "Net-(LED8-PadA)") (class "Default")
      (node (ref "LED8") (pin "A") (pinfunction "A_A") (pintype "passive"))
      (node (ref "R24") (pin "1") (pinfunction "1_1") (pintype "passive"))
    )
    (net (code "58") (name "Net-(LED9-PadA)") (class "Default")
      (node (ref "LED9") (pin "A") (pinfunction "A_A") (pintype "passive"))
      (node (ref "R25") (pin "1") (pinfunction "1_1") (pintype "passive"))
    )
    (net (code "59") (name "Net-(LED10-PadA)") (class "Default")
      (node (ref "LED10") (pin "A") (pinfunction "A_A") (pintype "passive"))
      (node (ref "R26") (pin "1") (pinfunction "1_1") (pintype "passive"))
    )
    (net (code "60") (name "Net-(Q1-D)") (class "Default")
      (node (ref "LED10") (pin "C") (pinfunction "C_C") (pintype "passive"))
      (node (ref "LED3") (pin "C") (pinfunction "C_C") (pintype "passive"))
      (node (ref "LED4") (pin "C") (pinfunction "C_C") (pintype "passive"))
      (node (ref "LED5") (pin "C") (pinfunction "C_C") (pintype "passive"))
      (node (ref "LED6") (pin "C") (pinfunction "C_C") (pintype "passive"))
      (node (ref "LED7") (pin "C") (pinfunction "C_C") (pintype "passive"))
      (node (ref "LED8") (pin "C") (pinfunction "C_C") (pintype "passive"))
      (node (ref "LED9") (pin "C") (pinfunction "C_C") (pintype "passive"))
      (node (ref "Q1") (pin "3") (pinfunction "D_3") (pintype "bidirectional"))
    )
    (net (code "61") (name "Net-(R5-Pad1)") (class "Default")
      (node (ref "R5") (pin "1") (pinfunction "1_1") (pintype "passive"))
      (node (ref "R6") (pin "1") (pinfunction "1_1") (pintype "passive"))
      (node (ref "R7") (pin "1") (pinfunction "1_1") (pintype "passive"))
      (node (ref "R8") (pin "1") (pinfunction "1_1") (pintype "passive"))
      (node (ref "T1") (pin "C") (pinfunction "C_C") (pintype "passive"))
    )
    (net (code "62") (name "Net-(R5-Pad2)") (class "Default")
      (node (ref "R5") (pin "2") (pinfunction "2_2") (pintype "passive"))
      (node (ref "U$10") (pin "P$2") (pinfunction "P$2_P$2") (pintype "bidirectional"))
    )
    (net (code "63") (name "Net-(R6-Pad2)") (class "Default")
      (node (ref "R6") (pin "2") (pinfunction "2_2") (pintype "passive"))
      (node (ref "U$13") (pin "P$2") (pinfunction "P$2_P$2") (pintype "bidirectional"))
    )
    (net (code "64") (name "Net-(R7-Pad2)") (class "Default")
      (node (ref "R7") (pin "2") (pinfunction "2_2") (pintype "passive"))
      (node (ref "U$12") (pin "P$2") (pinfunction "P$2_P$2") (pintype "bidirectional"))
    )
    (net (code "65") (name "Net-(R8-Pad2)") (class "Default")
      (node (ref "R8") (pin "2") (pinfunction "2_2") (pintype "passive"))
      (node (ref "U$8") (pin "P$2") (pinfunction "P$2_P$2") (pintype "bidirectional"))
    )
    (net (code "66") (name "Net-(T2-B)") (class "Default")
      (node (ref "R9") (pin "2") (pinfunction "2_2") (pintype "passive"))
      (node (ref "T1") (pin "E") (pinfunction "E_E") (pintype "passive"))
      (node (ref "T2") (pin "1") (pinfunction "B_1") (pintype "passive"))
      (node (ref "TP2") (pin "TP") (pinfunction "TP_TP") (pintype "input"))
    )
    (net (code "67") (name "Net-(T2-C)") (class "Default")
      (node (ref "R10") (pin "1") (pinfunction "1_1") (pintype "passive"))
      (node (ref "T1") (pin "B") (pinfunction "B_B") (pintype "passive"))
      (node (ref "T2") (pin "3") (pinfunction "C_3") (pintype "passive"))
    )
    (net (code "68") (name "Net-(U$1-CP1)") (class "Default")
      (node (ref "C23") (pin "2") (pinfunction "2_2") (pintype "passive"))
      (node (ref "U$1") (pin "P$20") (pinfunction "CP1_P$20") (pintype "passive"))
    )
    (net (code "69") (name "Net-(U$1-CP2)") (class "Default")
      (node (ref "C23") (pin "1") (pinfunction "1_1") (pintype "passive"))
      (node (ref "U$1") (pin "P$21") (pinfunction "CP2_P$21") (pintype "passive"))
    )
    (net (code "70") (name "Net-(U$1-VCP)") (class "Default")
      (node (ref "C24") (pin "2") (pinfunction "2_2") (pintype "passive"))
      (node (ref "U$1") (pin "P$19") (pinfunction "VCP_P$19") (pintype "output"))
    )
    (net (code "71") (name "Net-(U$1-VG)") (class "Default")
      (node (ref "C25") (pin "2") (pinfunction "2_2") (pintype "passive"))
      (node (ref "U$1") (pin "P$14") (pinfunction "VG_P$14") (pintype "power_in"))
    )
    (net (code "72") (name "Net-(U$3-CP1)") (class "Default")
      (node (ref "C26") (pin "2") (pinfunction "2_2") (pintype "passive"))
      (node (ref "U$3") (pin "P$20") (pinfunction "CP1_P$20") (pintype "passive"))
    )
    (net (code "73") (name "Net-(U$3-CP2)") (class "Default")
      (node (ref "C26") (pin "1") (pinfunction "1_1") (pintype "passive"))
      (node (ref "U$3") (pin "P$21") (pinfunction "CP2_P$21") (pintype "passive"))
    )
    (net (code "74") (name "Net-(U$3-VCP)") (class "Default")
      (node (ref "C27") (pin "2") (pinfunction "2_2") (pintype "passive"))
      (node (ref "U$3") (pin "P$19") (pinfunction "VCP_P$19") (pintype "output"))
    )
    (net (code "75") (name "Net-(U$3-VG)") (class "Default")
      (node (ref "C28") (pin "2") (pinfunction "2_2") (pintype "passive"))
      (node (ref "U$3") (pin "P$14") (pinfunction "VG_P$14") (pintype "power_in"))
    )
    (net (code "76") (name "Net-(U2-BST)") (class "Default")
      (node (ref "C12") (pin "1") (pinfunction "1_1") (pintype "passive"))
      (node (ref "U2") (pin "6") (pinfunction "BST_6") (pintype "bidirectional"))
    )
    (net (code "77") (name "Net-(U3A-PH0-OSC_IN)") (class "Default")
      (node (ref "C20") (pin "1") (pinfunction "1_1") (pintype "passive"))
      (node (ref "U3") (pin "5") (pinfunction "PH0-OSC_IN_5") (pintype "bidirectional"))
      (node (ref "Y1") (pin "3") (pinfunction "2_3") (pintype "passive"))
    )
    (net (code "78") (name "Net-(U3A-PH1-OSC_OUT)") (class "Default")
      (node (ref "C21") (pin "1") (pinfunction "1_1") (pintype "passive"))
      (node (ref "U3") (pin "6") (pinfunction "PH1-OSC_OUT_6") (pintype "bidirectional"))
      (node (ref "Y1") (pin "1") (pinfunction "1_1") (pintype "passive"))
    )
    (net (code "79") (name "Net-(U3B-VCAP_1)") (class "Default")
      (node (ref "C22") (pin "2") (pinfunction "2_2") (pintype "passive"))
      (node (ref "U3") (pin "30") (pinfunction "VCAP_1_30") (pintype "power_in"))
    )
    (net (code "80") (name "Net-(U4-DTR)") (class "Default")
      (node (ref "SJ1") (pin "1") (pinfunction "1_1") (pintype "passive"))
      (node (ref "U4") (pin "23") (pinfunction "DTR_23") (pintype "bidirectional"))
    )
    (net (code "81") (name "Net-(U4-RTS)") (class "Default")
      (node (ref "SJ2") (pin "1") (pinfunction "1_1") (pintype "passive"))
      (node (ref "U4") (pin "19") (pinfunction "RTS_19") (pintype "bidirectional"))
    )
    (net (code "82") (name "Net-(U4-VBUS)") (class "Default")
      (node (ref "R41") (pin "1") (pinfunction "1_1") (pintype "passive"))
      (node (ref "R42") (pin "2") (pinfunction "2_2") (pintype "passive"))
      (node (ref "U4") (pin "8") (pinfunction "VBUS_8") (pintype "bidirectional"))
    )
    (net (code "83") (name "Net-(U4-~{RSTB})") (class "Default")
      (node (ref "R40") (pin "2") (pinfunction "2_2") (pintype "passive"))
      (node (ref "U4") (pin "9") (pinfunction "~{RSTB}_9") (pintype "bidirectional"))
    )
    (net (code "84") (name "VCC") (class "Default")
      (node (ref "BATT") (pin "2") (pinfunction "2_2") (pintype "passive"))
      (node (ref "C10") (pin "+") (pinfunction "+_+") (pintype "passive"))
      (node (ref "C11") (pin "+") (pinfunction "+_+") (pintype "passive"))
      (node (ref "C13") (pin "2") (pinfunction "2_2") (pintype "passive"))
      (node (ref "C14") (pin "2") (pinfunction "2_2") (pintype "passive"))
      (node (ref "C24") (pin "1") (pinfunction "1_1") (pintype "passive"))
      (node (ref "C27") (pin "1") (pinfunction "1_1") (pintype "passive"))
      (node (ref "C4") (pin "1") (pinfunction "1_1") (pintype "passive"))
      (node (ref "C5") (pin "1") (pinfunction "1_1") (pintype "passive"))
      (node (ref "C6") (pin "1") (pinfunction "1_1") (pintype "passive"))
      (node (ref "C7") (pin "1") (pinfunction "1_1") (pintype "passive"))
      (node (ref "D1") (pin "C") (pinfunction "C_C") (pintype "passive"))
      (node (ref "U$1") (pin "P$23") (pinfunction "VIN_2_P$23") (pintype "power_in"))
      (node (ref "U$1") (pin "P$25") (pinfunction "VIN_P$25") (pintype "power_in"))
      (node (ref "U$10") (pin "P$1") (pinfunction "P$1_P$1") (pintype "bidirectional"))
      (node (ref "U$12") (pin "P$1") (pinfunction "P$1_P$1") (pintype "bidirectional"))
      (node (ref "U$13") (pin "P$1") (pinfunction "P$1_P$1") (pintype "bidirectional"))
      (node (ref "U$3") (pin "P$23") (pinfunction "VIN_2_P$23") (pintype "power_in"))
      (node (ref "U$3") (pin "P$25") (pinfunction "VIN_P$25") (pintype "power_in"))
      (node (ref "U$8") (pin "P$1") (pinfunction "P$1_P$1") (pintype "bidirectional"))
      (node (ref "U2") (pin "2") (pinfunction "EN_2") (pintype "bidirectional"))
      (node (ref "U2") (pin "3") (pinfunction "VIN_3") (pintype "bidirectional"))
    )
    (net (code "85") (name "unconnected-(U$1-NFAULT-PadP$1)") (class "Default")
      (node (ref "U$1") (pin "P$1") (pinfunction "NFAULT_P$1") (pintype "output"))
    )
    (net (code "86") (name "unconnected-(U$3-NFAULT-PadP$1)") (class "Default")
      (node (ref "U$3") (pin "P$1") (pinfunction "NFAULT_P$1") (pintype "output"))
    )
    (net (code "87") (name "unconnected-(U$6-INT1-PadP$4)") (class "Default")
      (node (ref "U$6") (pin "P$4") (pinfunction "INT1_P$4") (pintype "bidirectional"))
    )
    (net (code "88") (name "unconnected-(U$6-INT2-PadP$9)") (class "Default")
      (node (ref "U$6") (pin "P$9") (pinfunction "INT2_P$9") (pintype "bidirectional"))
    )
    (net (code "89") (name "unconnected-(U$6-NC1-PadP$10)") (class "Default")
      (node (ref "U$6") (pin "P$10") (pinfunction "NC1_P$10") (pintype "bidirectional"))
    )
    (net (code "90") (name "unconnected-(U$6-NC2-PadP$11)") (class "Default")
      (node (ref "U$6") (pin "P$11") (pinfunction "NC2_P$11") (pintype "bidirectional"))
    )
    (net (code "91") (name "unconnected-(U3A-PA8-Pad41)") (class "Default")
      (node (ref "U3") (pin "41") (pinfunction "PA8_41") (pintype "bidirectional"))
    )
    (net (code "92") (name "unconnected-(U3A-PA11-Pad44)") (class "Default")
      (node (ref "U3") (pin "44") (pinfunction "PA11_44") (pintype "bidirectional"))
    )
    (net (code "93") (name "unconnected-(U3A-PA12-Pad45)") (class "Default")
      (node (ref "U3") (pin "45") (pinfunction "PA12_45") (pintype "bidirectional"))
    )
    (net (code "94") (name "unconnected-(U3A-PA13-Pad46)") (class "Default")
      (node (ref "U3") (pin "46") (pinfunction "PA13_46") (pintype "bidirectional"))
    )
    (net (code "95") (name "unconnected-(U3A-PA14-Pad49)") (class "Default")
      (node (ref "U3") (pin "49") (pinfunction "PA14_49") (pintype "bidirectional"))
    )
    (net (code "96") (name "unconnected-(U3A-PA15-Pad50)") (class "Default")
      (node (ref "U3") (pin "50") (pinfunction "PA15_50") (pintype "bidirectional"))
    )
    (net (code "97") (name "unconnected-(U3A-PB3-Pad55)") (class "Default")
      (node (ref "U3") (pin "55") (pinfunction "PB3_55") (pintype "bidirectional"))
    )
    (net (code "98") (name "unconnected-(U3A-PB4-Pad56)") (class "Default")
      (node (ref "U3") (pin "56") (pinfunction "PB4_56") (pintype "bidirectional"))
    )
    (net (code "99") (name "unconnected-(U3A-PB12-Pad33)") (class "Default")
      (node (ref "U3") (pin "33") (pinfunction "PB12_33") (pintype "bidirectional"))
    )
    (net (code "100") (name "unconnected-(U3A-PB13-Pad34)") (class "Default")
      (node (ref "U3") (pin "34") (pinfunction "PB13_34") (pintype "bidirectional"))
    )
    (net (code "101") (name "unconnected-(U3A-PB14-Pad35)") (class "Default")
      (node (ref "U3") (pin "35") (pinfunction "PB14_35") (pintype "bidirectional"))
    )
    (net (code "102") (name "unconnected-(U3A-PB15-Pad36)") (class "Default")
      (node (ref "U3") (pin "36") (pinfunction "PB15_36") (pintype "bidirectional"))
    )
    (net (code "103") (name "unconnected-(U3A-PC13-Pad2)") (class "Default")
      (node (ref "U3") (pin "2") (pinfunction "PC13_2") (pintype "bidirectional"))
    )
    (net (code "104") (name "unconnected-(U3A-PC14-OSC32_IN-Pad3)") (class "Default")
      (node (ref "U3") (pin "3") (pinfunction "PC14-OSC32_IN_3") (pintype "bidirectional"))
    )
    (net (code "105") (name "unconnected-(U3A-PC15-OSC32_OUT-Pad4)") (class "Default")
      (node (ref "U3") (pin "4") (pinfunction "PC15-OSC32_OUT_4") (pintype "bidirectional"))
    )
    (net (code "106") (name "unconnected-(U3A-PD2-Pad54)") (class "Default")
      (node (ref "U3") (pin "54") (pinfunction "PD2_54") (pintype "bidirectional"))
    )
    (net (code "107") (name "unconnected-(U4-CTS-Pad18)") (class "Default")
      (node (ref "U4") (pin "18") (pinfunction "CTS_18") (pintype "bidirectional"))
    )
    (net (code "108") (name "unconnected-(U4-DCD-Pad24)") (class "Default")
      (node (ref "U4") (pin "24") (pinfunction "DCD_24") (pintype "bidirectional"))
    )
    (net (code "109") (name "unconnected-(U4-DSR-Pad22)") (class "Default")
      (node (ref "U4") (pin "22") (pinfunction "DSR_22") (pintype "bidirectional"))
    )
    (net (code "110") (name "unconnected-(U4-GPIO0{slash}TXT-Pad14)") (class "Default")
      (node (ref "U4") (pin "14") (pinfunction "GPIO0/TXT_14") (pintype "bidirectional"))
    )
    (net (code "111") (name "unconnected-(U4-GPIO1{slash}RXT-Pad13)") (class "Default")
      (node (ref "U4") (pin "13") (pinfunction "GPIO1/RXT_13") (pintype "bidirectional"))
    )
    (net (code "112") (name "unconnected-(U4-GPIO2{slash}RS485-Pad12)") (class "Default")
      (node (ref "U4") (pin "12") (pinfunction "GPIO2/RS485_12") (pintype "bidirectional"))
    )
    (net (code "113") (name "unconnected-(U4-GPIO3{slash}WAKEUP-Pad11)") (class "Default")
      (node (ref "U4") (pin "11") (pinfunction "GPIO3/WAKEUP_11") (pintype "bidirectional"))
    )
    (net (code "114") (name "unconnected-(U4-SUSPEND-Pad17)") (class "Default")
      (node (ref "U4") (pin "17") (pinfunction "SUSPEND_17") (pintype "bidirectional"))
    )
    (net (code "115") (name "unconnected-(U4-SUSPENDB-Pad15)") (class "Default")
      (node (ref "U4") (pin "15") (pinfunction "SUSPENDB_15") (pintype "bidirectional"))
    )
    (net (code "116") (name "unconnected-(U4-~{RI}{slash}CLK-Pad1)") (class "Default")
      (node (ref "U4") (pin "1") (pinfunction "~{RI}/CLK_1") (pintype "bidirectional"))
    )
  )
)
